# Brushless_2015RevB1_MagEnc.net
KiCad netlist of a schematic drawn in EAGLE
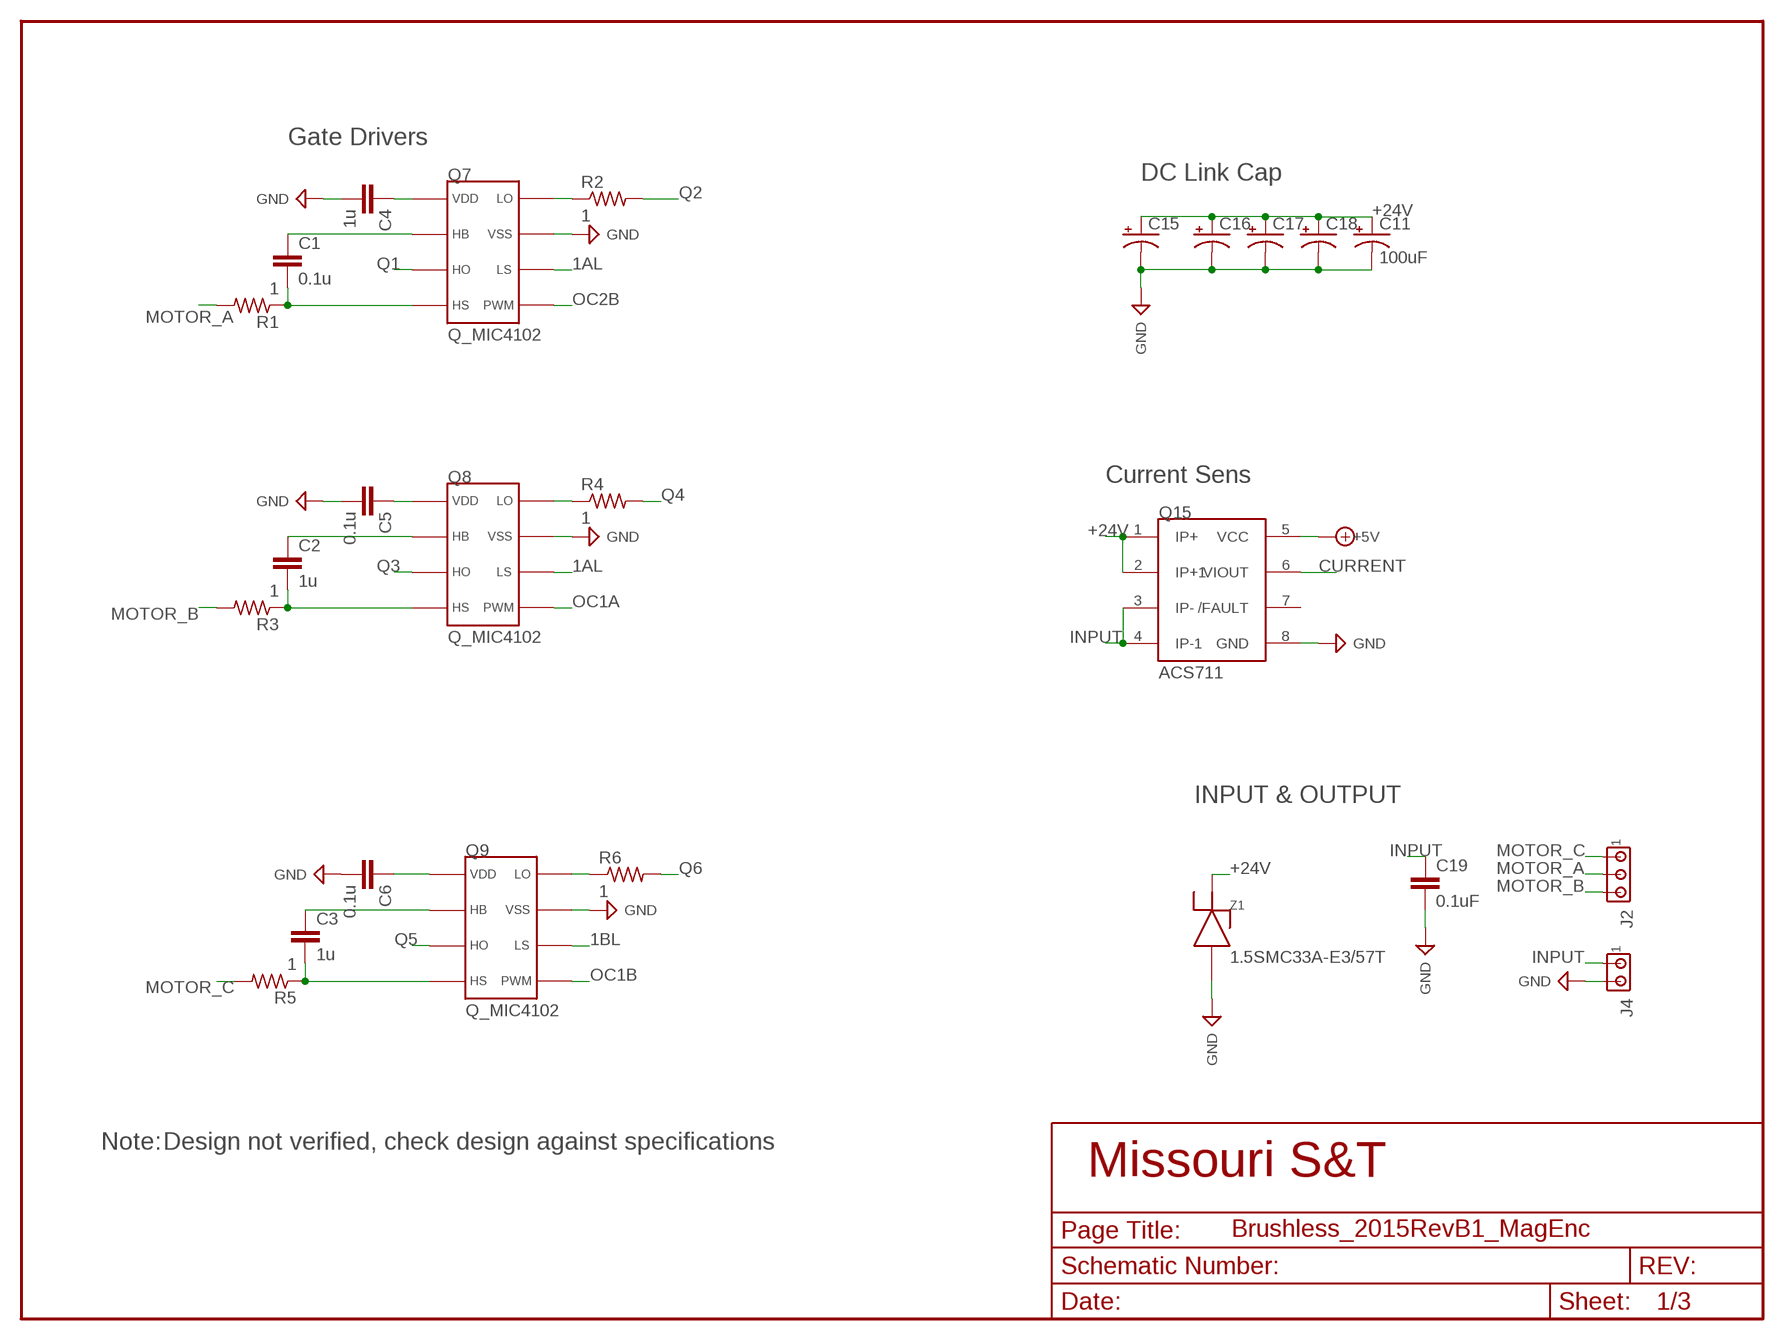
[diagram p0: schematic, sheet 1]
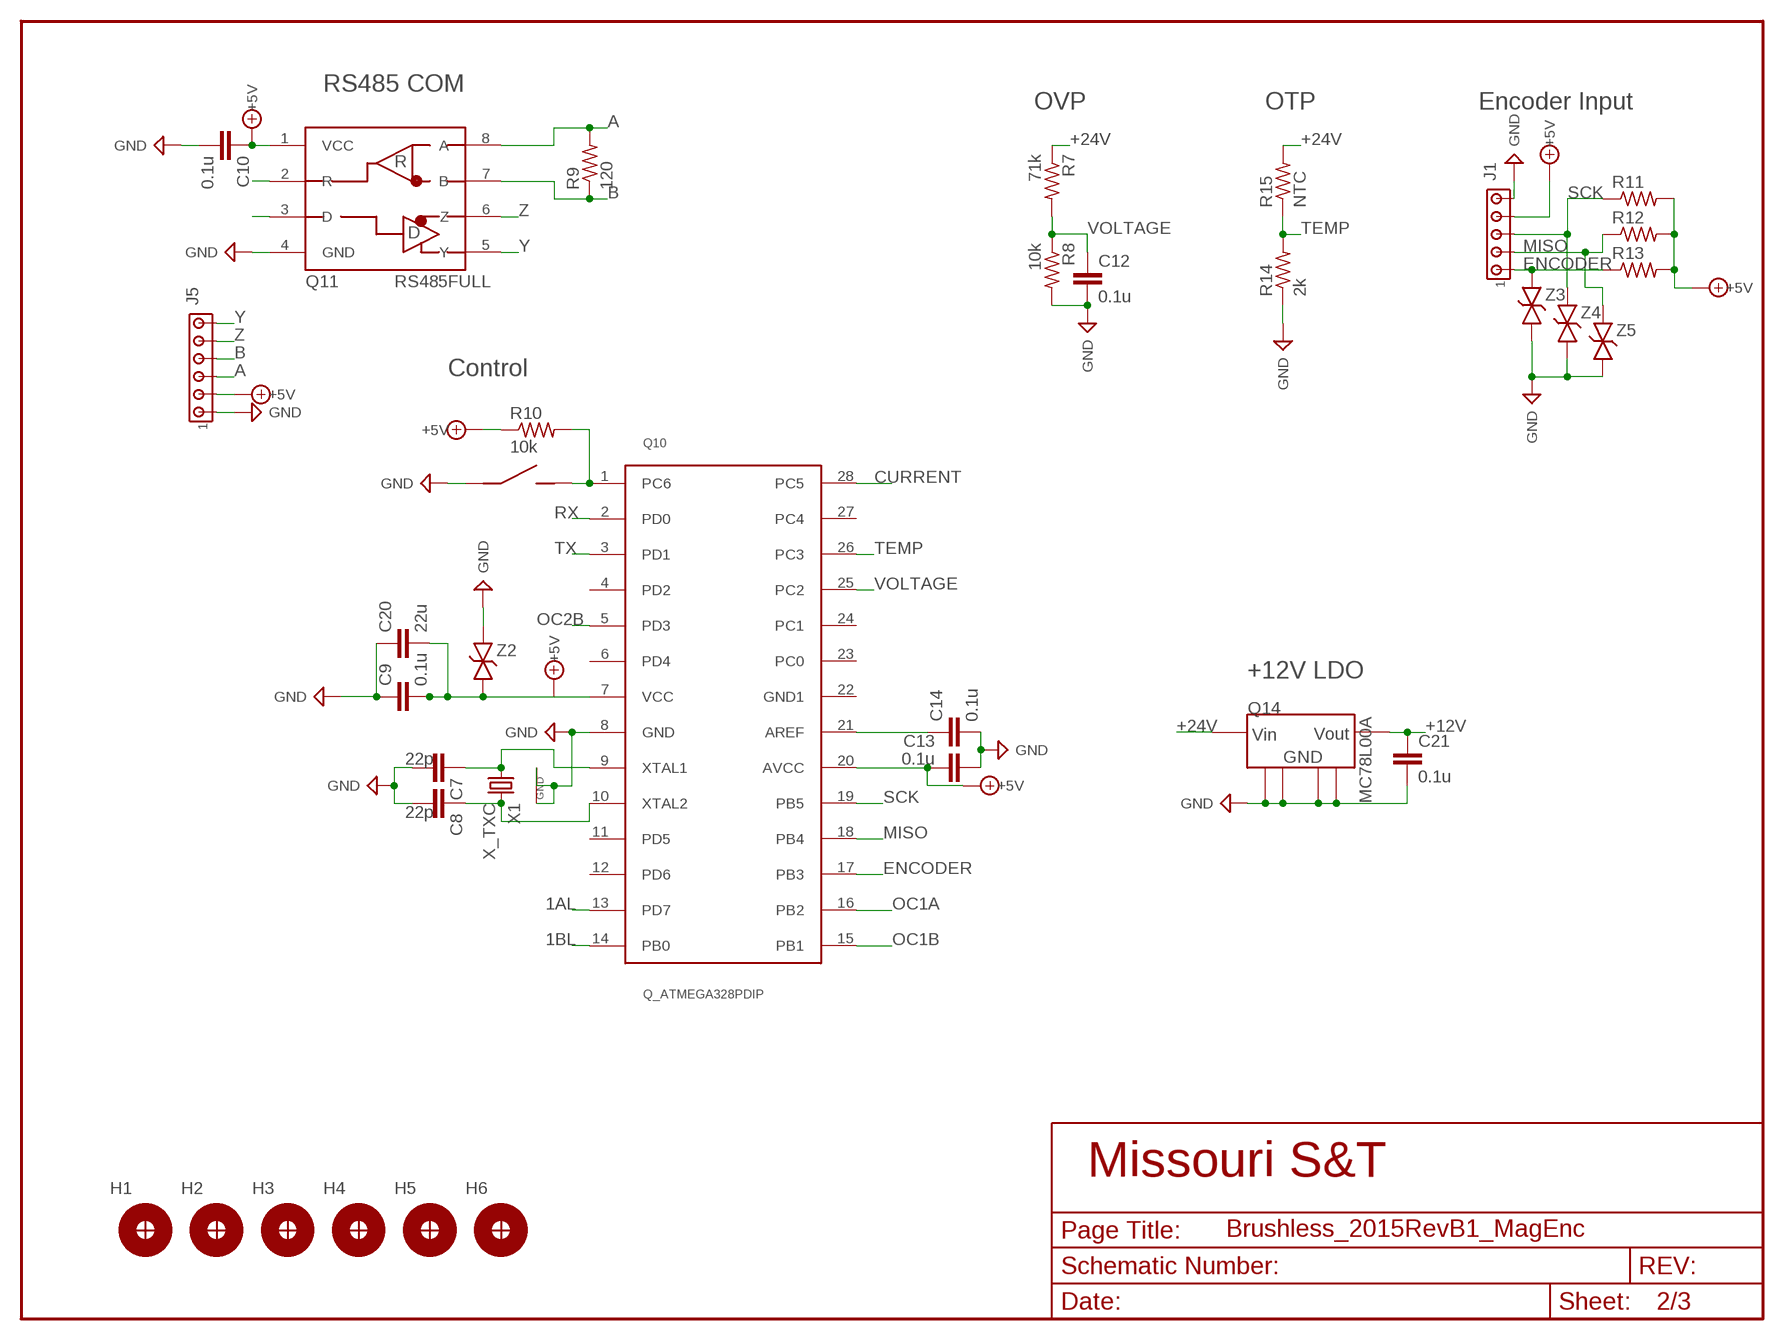
[diagram p1: schematic, sheet 2]
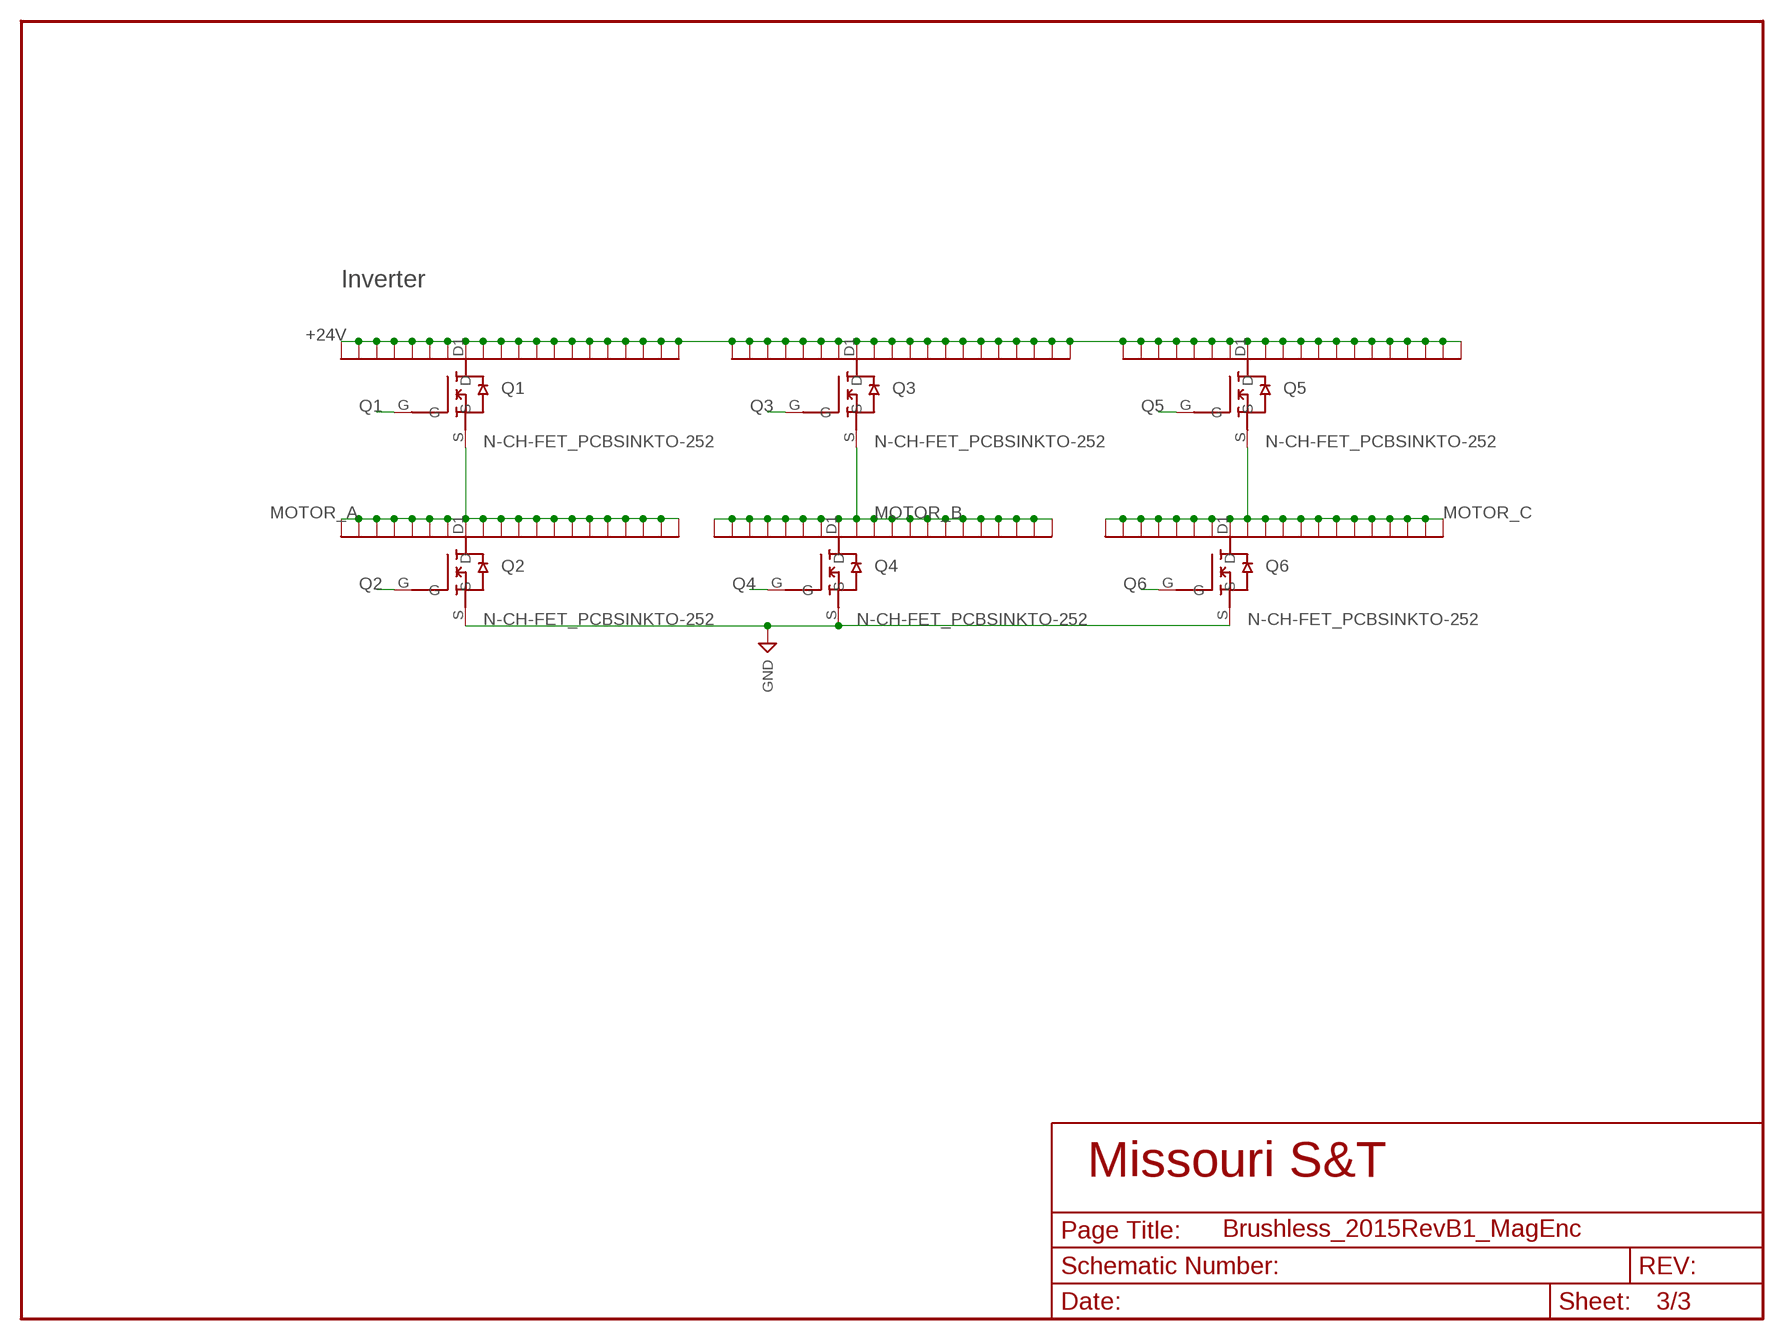
[diagram p2: schematic, sheet 3]

(export (version "E")
  (design (tool "Eeschema 10.0.6"))
  (components
    (comp (ref "C1")
      (value "0.1u")
      (footprint "eagle-import:C_1206")
      (libsource (lib "eagle-import") (part "Master_C_CAP_1206"))
    )
    (comp (ref "C2")
      (value "1u")
      (footprint "eagle-import:C_1206")
      (libsource (lib "eagle-import") (part "Master_C_CAP_1206"))
    )
    (comp (ref "C3")
      (value "1u")
      (footprint "eagle-import:C_1206")
      (libsource (lib "eagle-import") (part "Master_C_CAP_1206"))
    )
    (comp (ref "C4")
      (value "1u")
      (footprint "eagle-import:C_1206")
      (libsource (lib "eagle-import") (part "Master_C_CAP_1206"))
    )
    (comp (ref "C5")
      (value "0.1u")
      (footprint "eagle-import:C_1206")
      (libsource (lib "eagle-import") (part "Master_C_CAP_1206"))
    )
    (comp (ref "C6")
      (value "0.1u")
      (footprint "eagle-import:C_1206")
      (libsource (lib "eagle-import") (part "Master_C_CAP_1206"))
    )
    (comp (ref "C11")
      (value "100uF")
      (footprint "eagle-import:C_8MM")
      (libsource (lib "eagle-import") (part "CAP_POL8MM"))
    )
    (comp (ref "C15")
      (value "CAP_POL8MM")
      (footprint "eagle-import:C_8MM")
      (libsource (lib "eagle-import") (part "CAP_POL8MM"))
    )
    (comp (ref "C16")
      (value "CAP_POL8MM")
      (footprint "eagle-import:C_8MM")
      (libsource (lib "eagle-import") (part "CAP_POL8MM"))
    )
    (comp (ref "C17")
      (value "CAP_POL8MM")
      (footprint "eagle-import:C_8MM")
      (libsource (lib "eagle-import") (part "CAP_POL8MM"))
    )
    (comp (ref "C18")
      (value "CAP_POL8MM")
      (footprint "eagle-import:C_8MM")
      (libsource (lib "eagle-import") (part "CAP_POL8MM"))
    )
    (comp (ref "C19")
      (value "0.1uF")
      (footprint "eagle-import:C_1206")
      (libsource (lib "eagle-import") (part "C_CAP_1206"))
    )
    (comp (ref "J2")
      (value "J_MTA3P_156")
      (footprint "eagle-import:J_MTA156_3P")
      (libsource (lib "eagle-import") (part "J_MTA3P_156"))
    )
    (comp (ref "J4")
      (value "J_HDR1X2_MTA_156MIL")
      (footprint "eagle-import:J_MTA1X2_156MIL")
      (libsource (lib "eagle-import") (part "J_HDR1X2_MTA_156MIL"))
    )
    (comp (ref "Q7")
      (value "Q_MIC4102")
      (footprint "eagle-import:SOIC8")
      (libsource (lib "eagle-import") (part "Q_MIC4102"))
    )
    (comp (ref "Q8")
      (value "Q_MIC4102")
      (footprint "eagle-import:SOIC8")
      (libsource (lib "eagle-import") (part "Q_MIC4102"))
    )
    (comp (ref "Q9")
      (value "Q_MIC4102")
      (footprint "eagle-import:SOIC8")
      (libsource (lib "eagle-import") (part "Q_MIC4102"))
    )
    (comp (ref "Q15")
      (value "ACS711")
      (footprint "eagle-import:SOIC8")
      (libsource (lib "eagle-import") (part "ACS711SOIC"))
    )
    (comp (ref "R1")
      (value "1")
      (footprint "eagle-import:R_0805")
      (libsource (lib "eagle-import") (part "Master_R_RES_0805"))
    )
    (comp (ref "R2")
      (value "1")
      (footprint "eagle-import:R_0805")
      (libsource (lib "eagle-import") (part "Master_R_RES_0805"))
    )
    (comp (ref "R3")
      (value "1")
      (footprint "eagle-import:R_0805")
      (libsource (lib "eagle-import") (part "Master_R_RES_0805"))
    )
    (comp (ref "R4")
      (value "1")
      (footprint "eagle-import:R_0805")
      (libsource (lib "eagle-import") (part "Master_R_RES_0805"))
    )
    (comp (ref "R5")
      (value "1")
      (footprint "eagle-import:R_0805")
      (libsource (lib "eagle-import") (part "Master_R_RES_0805"))
    )
    (comp (ref "R6")
      (value "1")
      (footprint "eagle-import:R_0805")
      (libsource (lib "eagle-import") (part "Master_R_RES_0805"))
    )
    (comp (ref "Z1")
      (value "Z_TVSDO214")
      (footprint "eagle-import:DO-214AC")
      (libsource (lib "eagle-import") (part "Z_TVSDO214"))
    )
    (comp (ref "Q1")
      (value "N-CH-FET_PCBSINKTO-252")
      (footprint "eagle-import:TO-252-SINK")
      (libsource (lib "eagle-import") (part "N-CH-FET_PCBSINKTO-252"))
    )
    (comp (ref "Q2")
      (value "N-CH-FET_PCBSINKTO-252")
      (footprint "eagle-import:TO-252-SINK")
      (libsource (lib "eagle-import") (part "N-CH-FET_PCBSINKTO-252"))
    )
    (comp (ref "Q3")
      (value "N-CH-FET_PCBSINKTO-252")
      (footprint "eagle-import:TO-252-SINK")
      (libsource (lib "eagle-import") (part "N-CH-FET_PCBSINKTO-252"))
    )
    (comp (ref "Q4")
      (value "N-CH-FET_PCBSINKTO-252")
      (footprint "eagle-import:TO-252-SINK")
      (libsource (lib "eagle-import") (part "N-CH-FET_PCBSINKTO-252"))
    )
    (comp (ref "Q5")
      (value "N-CH-FET_PCBSINKTO-252")
      (footprint "eagle-import:TO-252-SINK")
      (libsource (lib "eagle-import") (part "N-CH-FET_PCBSINKTO-252"))
    )
    (comp (ref "Q6")
      (value "N-CH-FET_PCBSINKTO-252")
      (footprint "eagle-import:TO-252-SINK")
      (libsource (lib "eagle-import") (part "N-CH-FET_PCBSINKTO-252"))
    )
    (comp (ref "C7")
      (value "22p")
      (footprint "eagle-import:C_1206")
      (libsource (lib "eagle-import") (part "Master_C_CAP_1206"))
    )
    (comp (ref "C8")
      (value "22p")
      (footprint "eagle-import:C_1206")
      (libsource (lib "eagle-import") (part "Master_C_CAP_1206"))
    )
    (comp (ref "C9")
      (value "0.1u")
      (footprint "eagle-import:C_0805")
      (libsource (lib "eagle-import") (part "Master_C_CAP_0805"))
    )
    (comp (ref "C10")
      (value "0.1u")
      (footprint "eagle-import:C_0805")
      (libsource (lib "eagle-import") (part "Master_C_CAP_0805"))
    )
    (comp (ref "C12")
      (value "0.1u")
      (footprint "eagle-import:C_0805")
      (libsource (lib "eagle-import") (part "Master_C_CAP_0805"))
    )
    (comp (ref "C13")
      (value "0.1u")
      (footprint "eagle-import:C_1206")
      (libsource (lib "eagle-import") (part "C_CAP_1206"))
    )
    (comp (ref "C14")
      (value "0.1u")
      (footprint "eagle-import:C_0805")
      (libsource (lib "eagle-import") (part "Master_C_CAP_0805"))
    )
    (comp (ref "C20")
      (value "22u")
      (footprint "eagle-import:C_1206")
      (libsource (lib "eagle-import") (part "C_CAP_1206"))
    )
    (comp (ref "C21")
      (value "0.1u")
      (footprint "eagle-import:C_0805")
      (libsource (lib "eagle-import") (part "Master_C_CAP_0805"))
    )
    (comp (ref "H1")
      (value "H_MNTHOLE_#4")
      (footprint "eagle-import:H_MNTHOLE_#4")
      (libsource (lib "eagle-import") (part "H_MNTHOLE_#4"))
    )
    (comp (ref "H2")
      (value "H_MNTHOLE_#4")
      (footprint "eagle-import:H_MNTHOLE_#4")
      (libsource (lib "eagle-import") (part "H_MNTHOLE_#4"))
    )
    (comp (ref "H3")
      (value "H_MNTHOLE_#4")
      (footprint "eagle-import:H_MNTHOLE_#4")
      (libsource (lib "eagle-import") (part "H_MNTHOLE_#4"))
    )
    (comp (ref "H4")
      (value "H_MNTHOLE_#4")
      (footprint "eagle-import:H_MNTHOLE_#4")
      (libsource (lib "eagle-import") (part "H_MNTHOLE_#4"))
    )
    (comp (ref "H5")
      (value "H_MNTHOLE_#4")
      (footprint "eagle-import:H_MNTHOLE_#4")
      (libsource (lib "eagle-import") (part "H_MNTHOLE_#4"))
    )
    (comp (ref "H6")
      (value "H_MNTHOLE_#4")
      (footprint "eagle-import:H_MNTHOLE_#4")
      (libsource (lib "eagle-import") (part "H_MNTHOLE_#4"))
    )
    (comp (ref "J1")
      (value "J_MTA5P_100")
      (footprint "eagle-import:J_MTA100_5P")
      (libsource (lib "eagle-import") (part "J_MTA5P_100"))
    )
    (comp (ref "J3")
      (value "J_MC32857")
      (footprint "eagle-import:J_TOGGLE")
      (libsource (lib "eagle-import") (part "J_MC32857"))
    )
    (comp (ref "J5")
      (value "J_HDR1X6_MTA_100MIL")
      (footprint "eagle-import:J_MTA1X6_100MIL")
      (libsource (lib "eagle-import") (part "J_HDR1X6_MTA_100MIL"))
    )
    (comp (ref "Q10")
      (value "Q_ATMEGA328PDIP")
      (footprint "eagle-import:DIP28")
      (libsource (lib "eagle-import") (part "Q_ATMEGA328PDIP"))
    )
    (comp (ref "Q11")
      (value "RS485FULL")
      (footprint "eagle-import:SOIC8")
      (libsource (lib "eagle-import") (part "RS485FULL"))
    )
    (comp (ref "Q14")
      (value "MC78L00A")
      (footprint "eagle-import:SOIC8")
      (libsource (lib "eagle-import") (part "Q_LDOSOIC"))
    )
    (comp (ref "R7")
      (value "71k")
      (footprint "eagle-import:R_0805")
      (libsource (lib "eagle-import") (part "Master_R_RES_0805"))
    )
    (comp (ref "R8")
      (value "10k")
      (footprint "eagle-import:R_0805")
      (libsource (lib "eagle-import") (part "Master_R_RES_0805"))
    )
    (comp (ref "R9")
      (value "120")
      (footprint "eagle-import:R_0805")
      (libsource (lib "eagle-import") (part "Master_R_RES_0805"))
    )
    (comp (ref "R10")
      (value "10k")
      (footprint "eagle-import:R_0805")
      (libsource (lib "eagle-import") (part "R_RES_0805"))
    )
    (comp (ref "R11")
      (value "R_RES_1206")
      (footprint "eagle-import:R_1206")
      (libsource (lib "eagle-import") (part "R_RES_1206"))
    )
    (comp (ref "R12")
      (value "R_RES_1206")
      (footprint "eagle-import:R_1206")
      (libsource (lib "eagle-import") (part "R_RES_1206"))
    )
    (comp (ref "R13")
      (value "R_RES_1206")
      (footprint "eagle-import:R_1206")
      (libsource (lib "eagle-import") (part "R_RES_1206"))
    )
    (comp (ref "R14")
      (value "2k")
      (footprint "eagle-import:R_0805")
      (libsource (lib "eagle-import") (part "R_RES_0805"))
    )
    (comp (ref "R15")
      (value "NTC")
      (footprint "eagle-import:R_0805")
      (libsource (lib "eagle-import") (part "R_RES_0805"))
    )
    (comp (ref "X1")
      (value "X_TXC")
      (footprint "eagle-import:SMD_CRYSTAL")
      (libsource (lib "eagle-import") (part "X_TXC"))
    )
    (comp (ref "Z2")
      (value "Z_ESD0603")
      (footprint "eagle-import:0603")
      (libsource (lib "eagle-import") (part "Z_ESD0603"))
    )
    (comp (ref "Z3")
      (value "Z_ESD0603")
      (footprint "eagle-import:0603")
      (libsource (lib "eagle-import") (part "Z_ESD0603"))
    )
    (comp (ref "Z4")
      (value "Z_ESD0603")
      (footprint "eagle-import:0603")
      (libsource (lib "eagle-import") (part "Z_ESD0603"))
    )
    (comp (ref "Z5")
      (value "Z_ESD0603")
      (footprint "eagle-import:0603")
      (libsource (lib "eagle-import") (part "Z_ESD0603"))
    )
  )
  (nets
    (net (code "1") (name "+5V") (class "Default")
      (node (ref "C10") (pin "1") (pinfunction "1_1") (pintype "passive"))
      (node (ref "C13") (pin "1") (pinfunction "1_1") (pintype "passive"))
      (node (ref "C20") (pin "2") (pinfunction "2_2") (pintype "passive"))
      (node (ref "C9") (pin "2") (pinfunction "2_2") (pintype "passive"))
      (node (ref "J1") (pin "4") (pinfunction "4_4") (pintype "passive"))
      (node (ref "J5") (pin "2") (pinfunction "2_2") (pintype "passive"))
      (node (ref "Q10") (pin "20") (pinfunction "AVCC_20") (pintype "bidirectional"))
      (node (ref "Q10") (pin "7") (pinfunction "VCC_7") (pintype "bidirectional"))
      (node (ref "Q11") (pin "1") (pinfunction "VCC_1") (pintype "bidirectional"))
      (node (ref "Q15") (pin "5") (pinfunction "VCC_5") (pintype "bidirectional"))
      (node (ref "R10") (pin "1") (pinfunction "1_1") (pintype "passive"))
      (node (ref "R11") (pin "2") (pinfunction "2_2") (pintype "passive"))
      (node (ref "R12") (pin "2") (pinfunction "2_2") (pintype "passive"))
      (node (ref "R13") (pin "2") (pinfunction "2_2") (pintype "passive"))
      (node (ref "Z2") (pin "1") (pinfunction "P$1_1") (pintype "bidirectional"))
    )
    (net (code "2") (name "+12V") (class "Default")
      (node (ref "C21") (pin "1") (pinfunction "1_1") (pintype "passive"))
      (node (ref "C4") (pin "1") (pinfunction "1_1") (pintype "passive"))
      (node (ref "C5") (pin "1") (pinfunction "1_1") (pintype "passive"))
      (node (ref "C6") (pin "1") (pinfunction "1_1") (pintype "passive"))
      (node (ref "Q14") (pin "1") (pinfunction "VOUT_1") (pintype "bidirectional"))
      (node (ref "Q7") (pin "1") (pinfunction "VDD_1") (pintype "bidirectional"))
      (node (ref "Q8") (pin "1") (pinfunction "VDD_1") (pintype "bidirectional"))
      (node (ref "Q9") (pin "1") (pinfunction "VDD_1") (pintype "bidirectional"))
    )
    (net (code "3") (name "+24V") (class "Default")
      (node (ref "C11") (pin "+") (pinfunction "+_+") (pintype "passive"))
      (node (ref "C15") (pin "+") (pinfunction "+_+") (pintype "passive"))
      (node (ref "C16") (pin "+") (pinfunction "+_+") (pintype "passive"))
      (node (ref "C17") (pin "+") (pinfunction "+_+") (pintype "passive"))
      (node (ref "C18") (pin "+") (pinfunction "+_+") (pintype "passive"))
      (node (ref "Q1") (pin "D1") (pinfunction "D_D1") (pintype "bidirectional"))
      (node (ref "Q1") (pin "D10") (pinfunction "P$9_D10") (pintype "bidirectional"))
      (node (ref "Q1") (pin "D11") (pinfunction "P$10_D11") (pintype "bidirectional"))
      (node (ref "Q1") (pin "D12") (pinfunction "P$11_D12") (pintype "bidirectional"))
      (node (ref "Q1") (pin "D13") (pinfunction "P$12_D13") (pintype "bidirectional"))
      (node (ref "Q1") (pin "D14") (pinfunction "P$13_D14") (pintype "bidirectional"))
      (node (ref "Q1") (pin "D15") (pinfunction "P$14_D15") (pintype "bidirectional"))
      (node (ref "Q1") (pin "D16") (pinfunction "P$15_D16") (pintype "bidirectional"))
      (node (ref "Q1") (pin "D17") (pinfunction "P$16_D17") (pintype "bidirectional"))
      (node (ref "Q1") (pin "D18") (pinfunction "P$17_D18") (pintype "bidirectional"))
      (node (ref "Q1") (pin "D19") (pinfunction "P$18_D19") (pintype "bidirectional"))
      (node (ref "Q1") (pin "D2") (pinfunction "P$1_D2") (pintype "bidirectional"))
      (node (ref "Q1") (pin "D20") (pinfunction "P$19_D20") (pintype "bidirectional"))
      (node (ref "Q1") (pin "D3") (pinfunction "P$2_D3") (pintype "bidirectional"))
      (node (ref "Q1") (pin "D4") (pinfunction "P$3_D4") (pintype "bidirectional"))
      (node (ref "Q1") (pin "D5") (pinfunction "P$4_D5") (pintype "bidirectional"))
      (node (ref "Q1") (pin "D6") (pinfunction "P$5_D6") (pintype "bidirectional"))
      (node (ref "Q1") (pin "D7") (pinfunction "P$6_D7") (pintype "bidirectional"))
      (node (ref "Q1") (pin "D8") (pinfunction "P$7_D8") (pintype "bidirectional"))
      (node (ref "Q1") (pin "D9") (pinfunction "P$8_D9") (pintype "bidirectional"))
      (node (ref "Q14") (pin "8") (pinfunction "VIN_8") (pintype "bidirectional"))
      (node (ref "Q15") (pin "1") (pinfunction "IP+_1") (pintype "bidirectional"))
      (node (ref "Q15") (pin "2") (pinfunction "IP+1_2") (pintype "bidirectional"))
      (node (ref "Q3") (pin "D1") (pinfunction "D_D1") (pintype "bidirectional"))
      (node (ref "Q3") (pin "D10") (pinfunction "P$9_D10") (pintype "bidirectional"))
      (node (ref "Q3") (pin "D11") (pinfunction "P$10_D11") (pintype "bidirectional"))
      (node (ref "Q3") (pin "D12") (pinfunction "P$11_D12") (pintype "bidirectional"))
      (node (ref "Q3") (pin "D13") (pinfunction "P$12_D13") (pintype "bidirectional"))
      (node (ref "Q3") (pin "D14") (pinfunction "P$13_D14") (pintype "bidirectional"))
      (node (ref "Q3") (pin "D15") (pinfunction "P$14_D15") (pintype "bidirectional"))
      (node (ref "Q3") (pin "D16") (pinfunction "P$15_D16") (pintype "bidirectional"))
      (node (ref "Q3") (pin "D17") (pinfunction "P$16_D17") (pintype "bidirectional"))
      (node (ref "Q3") (pin "D18") (pinfunction "P$17_D18") (pintype "bidirectional"))
      (node (ref "Q3") (pin "D19") (pinfunction "P$18_D19") (pintype "bidirectional"))
      (node (ref "Q3") (pin "D2") (pinfunction "P$1_D2") (pintype "bidirectional"))
      (node (ref "Q3") (pin "D20") (pinfunction "P$19_D20") (pintype "bidirectional"))
      (node (ref "Q3") (pin "D3") (pinfunction "P$2_D3") (pintype "bidirectional"))
      (node (ref "Q3") (pin "D4") (pinfunction "P$3_D4") (pintype "bidirectional"))
      (node (ref "Q3") (pin "D5") (pinfunction "P$4_D5") (pintype "bidirectional"))
      (node (ref "Q3") (pin "D6") (pinfunction "P$5_D6") (pintype "bidirectional"))
      (node (ref "Q3") (pin "D7") (pinfunction "P$6_D7") (pintype "bidirectional"))
      (node (ref "Q3") (pin "D8") (pinfunction "P$7_D8") (pintype "bidirectional"))
      (node (ref "Q3") (pin "D9") (pinfunction "P$8_D9") (pintype "bidirectional"))
      (node (ref "Q5") (pin "D1") (pinfunction "D_D1") (pintype "bidirectional"))
      (node (ref "Q5") (pin "D10") (pinfunction "P$9_D10") (pintype "bidirectional"))
      (node (ref "Q5") (pin "D11") (pinfunction "P$10_D11") (pintype "bidirectional"))
      (node (ref "Q5") (pin "D12") (pinfunction "P$11_D12") (pintype "bidirectional"))
      (node (ref "Q5") (pin "D13") (pinfunction "P$12_D13") (pintype "bidirectional"))
      (node (ref "Q5") (pin "D14") (pinfunction "P$13_D14") (pintype "bidirectional"))
      (node (ref "Q5") (pin "D15") (pinfunction "P$14_D15") (pintype "bidirectional"))
      (node (ref "Q5") (pin "D16") (pinfunction "P$15_D16") (pintype "bidirectional"))
      (node (ref "Q5") (pin "D17") (pinfunction "P$16_D17") (pintype "bidirectional"))
      (node (ref "Q5") (pin "D18") (pinfunction "P$17_D18") (pintype "bidirectional"))
      (node (ref "Q5") (pin "D19") (pinfunction "P$18_D19") (pintype "bidirectional"))
      (node (ref "Q5") (pin "D2") (pinfunction "P$1_D2") (pintype "bidirectional"))
      (node (ref "Q5") (pin "D20") (pinfunction "P$19_D20") (pintype "bidirectional"))
      (node (ref "Q5") (pin "D3") (pinfunction "P$2_D3") (pintype "bidirectional"))
      (node (ref "Q5") (pin "D4") (pinfunction "P$3_D4") (pintype "bidirectional"))
      (node (ref "Q5") (pin "D5") (pinfunction "P$4_D5") (pintype "bidirectional"))
      (node (ref "Q5") (pin "D6") (pinfunction "P$5_D6") (pintype "bidirectional"))
      (node (ref "Q5") (pin "D7") (pinfunction "P$6_D7") (pintype "bidirectional"))
      (node (ref "Q5") (pin "D8") (pinfunction "P$7_D8") (pintype "bidirectional"))
      (node (ref "Q5") (pin "D9") (pinfunction "P$8_D9") (pintype "bidirectional"))
      (node (ref "R15") (pin "2") (pinfunction "2_2") (pintype "passive"))
      (node (ref "R7") (pin "1") (pinfunction "1_1") (pintype "passive"))
      (node (ref "Z1") (pin "C") (pinfunction "C_C") (pintype "bidirectional"))
    )
    (net (code "4") (name "1AL") (class "Default")
      (node (ref "Q10") (pin "13") (pinfunction "PD7_13") (pintype "bidirectional"))
      (node (ref "Q7") (pin "6") (pinfunction "LS_6") (pintype "bidirectional"))
      (node (ref "Q8") (pin "6") (pinfunction "LS_6") (pintype "bidirectional"))
    )
    (net (code "5") (name "1BL") (class "Default")
      (node (ref "Q10") (pin "14") (pinfunction "PB0_14") (pintype "bidirectional"))
      (node (ref "Q9") (pin "6") (pinfunction "LS_6") (pintype "bidirectional"))
    )
    (net (code "6") (name "A") (class "Default")
      (node (ref "J5") (pin "3") (pinfunction "3_3") (pintype "passive"))
      (node (ref "Q11") (pin "8") (pinfunction "A_8") (pintype "bidirectional"))
      (node (ref "R9") (pin "2") (pinfunction "2_2") (pintype "passive"))
    )
    (net (code "7") (name "B") (class "Default")
      (node (ref "J5") (pin "4") (pinfunction "4_4") (pintype "passive"))
      (node (ref "Q11") (pin "7") (pinfunction "B_7") (pintype "bidirectional"))
      (node (ref "R9") (pin "1") (pinfunction "1_1") (pintype "passive"))
    )
    (net (code "8") (name "CURRENT") (class "Default")
      (node (ref "Q10") (pin "28") (pinfunction "PC5_28") (pintype "bidirectional"))
      (node (ref "Q15") (pin "6") (pinfunction "VIOUT_6") (pintype "bidirectional"))
    )
    (net (code "9") (name "ENCODER") (class "Default")
      (node (ref "J1") (pin "1") (pinfunction "1_1") (pintype "passive"))
      (node (ref "Q10") (pin "17") (pinfunction "PB3_17") (pintype "bidirectional"))
      (node (ref "R13") (pin "1") (pinfunction "1_1") (pintype "passive"))
      (node (ref "Z3") (pin "2") (pinfunction "P$2_2") (pintype "bidirectional"))
    )
    (net (code "10") (name "GND") (class "Default")
      (node (ref "C10") (pin "2") (pinfunction "2_2") (pintype "passive"))
      (node (ref "C11") (pin "-") (pinfunction "-_-") (pintype "passive"))
      (node (ref "C12") (pin "2") (pinfunction "2_2") (pintype "passive"))
      (node (ref "C13") (pin "2") (pinfunction "2_2") (pintype "passive"))
      (node (ref "C14") (pin "2") (pinfunction "2_2") (pintype "passive"))
      (node (ref "C15") (pin "-") (pinfunction "-_-") (pintype "passive"))
      (node (ref "C16") (pin "-") (pinfunction "-_-") (pintype "passive"))
      (node (ref "C17") (pin "-") (pinfunction "-_-") (pintype "passive"))
      (node (ref "C18") (pin "-") (pinfunction "-_-") (pintype "passive"))
      (node (ref "C19") (pin "2") (pinfunction "2_2") (pintype "passive"))
      (node (ref "C20") (pin "1") (pinfunction "1_1") (pintype "passive"))
      (node (ref "C21") (pin "2") (pinfunction "2_2") (pintype "passive"))
      (node (ref "C4") (pin "2") (pinfunction "2_2") (pintype "passive"))
      (node (ref "C5") (pin "2") (pinfunction "2_2") (pintype "passive"))
      (node (ref "C6") (pin "2") (pinfunction "2_2") (pintype "passive"))
      (node (ref "C7") (pin "2") (pinfunction "2_2") (pintype "passive"))
      (node (ref "C8") (pin "2") (pinfunction "2_2") (pintype "passive"))
      (node (ref "C9") (pin "1") (pinfunction "1_1") (pintype "passive"))
      (node (ref "J1") (pin "5") (pinfunction "5_5") (pintype "passive"))
      (node (ref "J3") (pin "P$1") (pinfunction "1_P$1") (pintype "bidirectional"))
      (node (ref "J4") (pin "2") (pinfunction "2_2") (pintype "passive"))
      (node (ref "J5") (pin "1") (pinfunction "1_1") (pintype "passive"))
      (node (ref "Q10") (pin "8") (pinfunction "GND_8") (pintype "bidirectional"))
      (node (ref "Q11") (pin "4") (pinfunction "GND_4") (pintype "bidirectional"))
      (node (ref "Q14") (pin "2") (pinfunction "GND_2") (pintype "bidirectional"))
      (node (ref "Q14") (pin "3") (pinfunction "GND1_3") (pintype "bidirectional"))
      (node (ref "Q14") (pin "6") (pinfunction "GND3_6") (pintype "bidirectional"))
      (node (ref "Q14") (pin "7") (pinfunction "GND2_7") (pintype "bidirectional"))
      (node (ref "Q15") (pin "8") (pinfunction "GND_8") (pintype "bidirectional"))
      (node (ref "Q2") (pin "S") (pinfunction "S_S") (pintype "bidirectional"))
      (node (ref "Q4") (pin "S") (pinfunction "S_S") (pintype "bidirectional"))
      (node (ref "Q6") (pin "S") (pinfunction "S_S") (pintype "bidirectional"))
      (node (ref "Q7") (pin "7") (pinfunction "VSS_7") (pintype "bidirectional"))
      (node (ref "Q8") (pin "7") (pinfunction "VSS_7") (pintype "bidirectional"))
      (node (ref "Q9") (pin "7") (pinfunction "VSS_7") (pintype "bidirectional"))
      (node (ref "R14") (pin "1") (pinfunction "1_1") (pintype "passive"))
      (node (ref "R8") (pin "2") (pinfunction "2_2") (pintype "passive"))
      (node (ref "X1") (pin "2") (pinfunction "GND1_2") (pintype "bidirectional"))
      (node (ref "X1") (pin "4") (pinfunction "GND2_4") (pintype "bidirectional"))
      (node (ref "Z1") (pin "A") (pinfunction "A_A") (pintype "bidirectional"))
      (node (ref "Z2") (pin "2") (pinfunction "P$2_2") (pintype "bidirectional"))
      (node (ref "Z3") (pin "1") (pinfunction "P$1_1") (pintype "bidirectional"))
      (node (ref "Z4") (pin "1") (pinfunction "P$1_1") (pintype "bidirectional"))
      (node (ref "Z5") (pin "1") (pinfunction "P$1_1") (pintype "bidirectional"))
    )
    (net (code "11") (name "INPUT") (class "Default")
      (node (ref "C19") (pin "1") (pinfunction "1_1") (pintype "passive"))
      (node (ref "J4") (pin "1") (pinfunction "1_1") (pintype "passive"))
      (node (ref "Q15") (pin "3") (pinfunction "IP-_3") (pintype "bidirectional"))
      (node (ref "Q15") (pin "4") (pinfunction "IP-1_4") (pintype "bidirectional"))
    )
    (net (code "12") (name "MISO") (class "Default")
      (node (ref "J1") (pin "2") (pinfunction "2_2") (pintype "passive"))
      (node (ref "Q10") (pin "18") (pinfunction "PB4_18") (pintype "bidirectional"))
      (node (ref "R12") (pin "1") (pinfunction "1_1") (pintype "passive"))
      (node (ref "Z5") (pin "2") (pinfunction "P$2_2") (pintype "bidirectional"))
    )
    (net (code "13") (name "MOTOR_A") (class "Default")
      (node (ref "J2") (pin "2") (pinfunction "2_2") (pintype "passive"))
      (node (ref "Q1") (pin "S") (pinfunction "S_S") (pintype "bidirectional"))
      (node (ref "Q2") (pin "D1") (pinfunction "D_D1") (pintype "bidirectional"))
      (node (ref "Q2") (pin "D10") (pinfunction "P$9_D10") (pintype "bidirectional"))
      (node (ref "Q2") (pin "D11") (pinfunction "P$10_D11") (pintype "bidirectional"))
      (node (ref "Q2") (pin "D12") (pinfunction "P$11_D12") (pintype "bidirectional"))
      (node (ref "Q2") (pin "D13") (pinfunction "P$12_D13") (pintype "bidirectional"))
      (node (ref "Q2") (pin "D14") (pinfunction "P$13_D14") (pintype "bidirectional"))
      (node (ref "Q2") (pin "D15") (pinfunction "P$14_D15") (pintype "bidirectional"))
      (node (ref "Q2") (pin "D16") (pinfunction "P$15_D16") (pintype "bidirectional"))
      (node (ref "Q2") (pin "D17") (pinfunction "P$16_D17") (pintype "bidirectional"))
      (node (ref "Q2") (pin "D18") (pinfunction "P$17_D18") (pintype "bidirectional"))
      (node (ref "Q2") (pin "D19") (pinfunction "P$18_D19") (pintype "bidirectional"))
      (node (ref "Q2") (pin "D2") (pinfunction "P$1_D2") (pintype "bidirectional"))
      (node (ref "Q2") (pin "D20") (pinfunction "P$19_D20") (pintype "bidirectional"))
      (node (ref "Q2") (pin "D3") (pinfunction "P$2_D3") (pintype "bidirectional"))
      (node (ref "Q2") (pin "D4") (pinfunction "P$3_D4") (pintype "bidirectional"))
      (node (ref "Q2") (pin "D5") (pinfunction "P$4_D5") (pintype "bidirectional"))
      (node (ref "Q2") (pin "D6") (pinfunction "P$5_D6") (pintype "bidirectional"))
      (node (ref "Q2") (pin "D7") (pinfunction "P$6_D7") (pintype "bidirectional"))
      (node (ref "Q2") (pin "D8") (pinfunction "P$7_D8") (pintype "bidirectional"))
      (node (ref "Q2") (pin "D9") (pinfunction "P$8_D9") (pintype "bidirectional"))
      (node (ref "R1") (pin "2") (pinfunction "2_2") (pintype "passive"))
    )
    (net (code "14") (name "MOTOR_B") (class "Default")
      (node (ref "J2") (pin "3") (pinfunction "3_3") (pintype "passive"))
      (node (ref "Q3") (pin "S") (pinfunction "S_S") (pintype "bidirectional"))
      (node (ref "Q4") (pin "D1") (pinfunction "D_D1") (pintype "bidirectional"))
      (node (ref "Q4") (pin "D10") (pinfunction "P$9_D10") (pintype "bidirectional"))
      (node (ref "Q4") (pin "D11") (pinfunction "P$10_D11") (pintype "bidirectional"))
      (node (ref "Q4") (pin "D12") (pinfunction "P$11_D12") (pintype "bidirectional"))
      (node (ref "Q4") (pin "D13") (pinfunction "P$12_D13") (pintype "bidirectional"))
      (node (ref "Q4") (pin "D14") (pinfunction "P$13_D14") (pintype "bidirectional"))
      (node (ref "Q4") (pin "D15") (pinfunction "P$14_D15") (pintype "bidirectional"))
      (node (ref "Q4") (pin "D16") (pinfunction "P$15_D16") (pintype "bidirectional"))
      (node (ref "Q4") (pin "D17") (pinfunction "P$16_D17") (pintype "bidirectional"))
      (node (ref "Q4") (pin "D18") (pinfunction "P$17_D18") (pintype "bidirectional"))
      (node (ref "Q4") (pin "D19") (pinfunction "P$18_D19") (pintype "bidirectional"))
      (node (ref "Q4") (pin "D2") (pinfunction "P$1_D2") (pintype "bidirectional"))
      (node (ref "Q4") (pin "D20") (pinfunction "P$19_D20") (pintype "bidirectional"))
      (node (ref "Q4") (pin "D3") (pinfunction "P$2_D3") (pintype "bidirectional"))
      (node (ref "Q4") (pin "D4") (pinfunction "P$3_D4") (pintype "bidirectional"))
      (node (ref "Q4") (pin "D5") (pinfunction "P$4_D5") (pintype "bidirectional"))
      (node (ref "Q4") (pin "D6") (pinfunction "P$5_D6") (pintype "bidirectional"))
      (node (ref "Q4") (pin "D7") (pinfunction "P$6_D7") (pintype "bidirectional"))
      (node (ref "Q4") (pin "D8") (pinfunction "P$7_D8") (pintype "bidirectional"))
      (node (ref "Q4") (pin "D9") (pinfunction "P$8_D9") (pintype "bidirectional"))
      (node (ref "R3") (pin "2") (pinfunction "2_2") (pintype "passive"))
    )
    (net (code "15") (name "MOTOR_C") (class "Default")
      (node (ref "J2") (pin "1") (pinfunction "1_1") (pintype "passive"))
      (node (ref "Q5") (pin "S") (pinfunction "S_S") (pintype "bidirectional"))
      (node (ref "Q6") (pin "D1") (pinfunction "D_D1") (pintype "bidirectional"))
      (node (ref "Q6") (pin "D10") (pinfunction "P$9_D10") (pintype "bidirectional"))
      (node (ref "Q6") (pin "D11") (pinfunction "P$10_D11") (pintype "bidirectional"))
      (node (ref "Q6") (pin "D12") (pinfunction "P$11_D12") (pintype "bidirectional"))
      (node (ref "Q6") (pin "D13") (pinfunction "P$12_D13") (pintype "bidirectional"))
      (node (ref "Q6") (pin "D14") (pinfunction "P$13_D14") (pintype "bidirectional"))
      (node (ref "Q6") (pin "D15") (pinfunction "P$14_D15") (pintype "bidirectional"))
      (node (ref "Q6") (pin "D16") (pinfunction "P$15_D16") (pintype "bidirectional"))
      (node (ref "Q6") (pin "D17") (pinfunction "P$16_D17") (pintype "bidirectional"))
      (node (ref "Q6") (pin "D18") (pinfunction "P$17_D18") (pintype "bidirectional"))
      (node (ref "Q6") (pin "D19") (pinfunction "P$18_D19") (pintype "bidirectional"))
      (node (ref "Q6") (pin "D2") (pinfunction "P$1_D2") (pintype "bidirectional"))
      (node (ref "Q6") (pin "D20") (pinfunction "P$19_D20") (pintype "bidirectional"))
      (node (ref "Q6") (pin "D3") (pinfunction "P$2_D3") (pintype "bidirectional"))
      (node (ref "Q6") (pin "D4") (pinfunction "P$3_D4") (pintype "bidirectional"))
      (node (ref "Q6") (pin "D5") (pinfunction "P$4_D5") (pintype "bidirectional"))
      (node (ref "Q6") (pin "D6") (pinfunction "P$5_D6") (pintype "bidirectional"))
      (node (ref "Q6") (pin "D7") (pinfunction "P$6_D7") (pintype "bidirectional"))
      (node (ref "Q6") (pin "D8") (pinfunction "P$7_D8") (pintype "bidirectional"))
      (node (ref "Q6") (pin "D9") (pinfunction "P$8_D9") (pintype "bidirectional"))
      (node (ref "R5") (pin "2") (pinfunction "2_2") (pintype "passive"))
    )
    (net (code "16") (name "Net-(J3-2)") (class "Default")
      (node (ref "J3") (pin "P$2") (pinfunction "2_P$2") (pintype "bidirectional"))
      (node (ref "Q10") (pin "1") (pinfunction "PC6_1") (pintype "bidirectional"))
      (node (ref "R10") (pin "2") (pinfunction "2_2") (pintype "passive"))
    )
    (net (code "17") (name "Net-(Q7-HB)") (class "Default")
      (node (ref "C1") (pin "1") (pinfunction "1_1") (pintype "passive"))
      (node (ref "Q7") (pin "2") (pinfunction "HB_2") (pintype "bidirectional"))
    )
    (net (code "18") (name "Net-(Q7-HS)") (class "Default")
      (node (ref "C1") (pin "2") (pinfunction "2_2") (pintype "passive"))
      (node (ref "Q7") (pin "4") (pinfunction "HS_4") (pintype "bidirectional"))
      (node (ref "R1") (pin "1") (pinfunction "1_1") (pintype "passive"))
    )
    (net (code "19") (name "Net-(Q7-LO)") (class "Default")
      (node (ref "Q7") (pin "8") (pinfunction "LO_8") (pintype "bidirectional"))
      (node (ref "R2") (pin "1") (pinfunction "1_1") (pintype "passive"))
    )
    (net (code "20") (name "Net-(Q8-HB)") (class "Default")
      (node (ref "C2") (pin "1") (pinfunction "1_1") (pintype "passive"))
      (node (ref "Q8") (pin "2") (pinfunction "HB_2") (pintype "bidirectional"))
    )
    (net (code "21") (name "Net-(Q8-HS)") (class "Default")
      (node (ref "C2") (pin "2") (pinfunction "2_2") (pintype "passive"))
      (node (ref "Q8") (pin "4") (pinfunction "HS_4") (pintype "bidirectional"))
      (node (ref "R3") (pin "1") (pinfunction "1_1") (pintype "passive"))
    )
    (net (code "22") (name "Net-(Q8-LO)") (class "Default")
      (node (ref "Q8") (pin "8") (pinfunction "LO_8") (pintype "bidirectional"))
      (node (ref "R4") (pin "1") (pinfunction "1_1") (pintype "passive"))
    )
    (net (code "23") (name "Net-(Q9-HB)") (class "Default")
      (node (ref "C3") (pin "1") (pinfunction "1_1") (pintype "passive"))
      (node (ref "Q9") (pin "2") (pinfunction "HB_2") (pintype "bidirectional"))
    )
    (net (code "24") (name "Net-(Q9-HS)") (class "Default")
      (node (ref "C3") (pin "2") (pinfunction "2_2") (pintype "passive"))
      (node (ref "Q9") (pin "4") (pinfunction "HS_4") (pintype "bidirectional"))
      (node (ref "R5") (pin "1") (pinfunction "1_1") (pintype "passive"))
    )
    (net (code "25") (name "Net-(Q9-LO)") (class "Default")
      (node (ref "Q9") (pin "8") (pinfunction "LO_8") (pintype "bidirectional"))
      (node (ref "R6") (pin "1") (pinfunction "1_1") (pintype "passive"))
    )
    (net (code "26") (name "Net-(Q10-AREF)") (class "Default")
      (node (ref "C14") (pin "1") (pinfunction "1_1") (pintype "passive"))
      (node (ref "Q10") (pin "21") (pinfunction "AREF_21") (pintype "bidirectional"))
    )
    (net (code "27") (name "Net-(Q10-XTAL1)") (class "Default")
      (node (ref "C7") (pin "1") (pinfunction "1_1") (pintype "passive"))
      (node (ref "Q10") (pin "9") (pinfunction "XTAL1_9") (pintype "bidirectional"))
      (node (ref "X1") (pin "1") (pinfunction "1_1") (pintype "passive"))
    )
    (net (code "28") (name "Net-(Q10-XTAL2)") (class "Default")
      (node (ref "C8") (pin "1") (pinfunction "1_1") (pintype "passive"))
      (node (ref "Q10") (pin "10") (pinfunction "XTAL2_10") (pintype "bidirectional"))
      (node (ref "X1") (pin "3") (pinfunction "2_3") (pintype "passive"))
    )
    (net (code "29") (name "OC1A") (class "Default")
      (node (ref "Q10") (pin "16") (pinfunction "PB2_16") (pintype "bidirectional"))
      (node (ref "Q8") (pin "5") (pinfunction "PWM_5") (pintype "bidirectional"))
    )
    (net (code "30") (name "OC1B") (class "Default")
      (node (ref "Q10") (pin "15") (pinfunction "PB1_15") (pintype "bidirectional"))
      (node (ref "Q9") (pin "5") (pinfunction "PWM_5") (pintype "bidirectional"))
    )
    (net (code "31") (name "OC2B") (class "Default")
      (node (ref "Q10") (pin "5") (pinfunction "PD3_5") (pintype "bidirectional"))
      (node (ref "Q7") (pin "5") (pinfunction "PWM_5") (pintype "bidirectional"))
    )
    (net (code "32") (name "Q1") (class "Default")
      (node (ref "Q1") (pin "G") (pinfunction "G_G") (pintype "bidirectional"))
      (node (ref "Q7") (pin "3") (pinfunction "HO_3") (pintype "bidirectional"))
    )
    (net (code "33") (name "Q2") (class "Default")
      (node (ref "Q2") (pin "G") (pinfunction "G_G") (pintype "bidirectional"))
      (node (ref "R2") (pin "2") (pinfunction "2_2") (pintype "passive"))
    )
    (net (code "34") (name "Q3") (class "Default")
      (node (ref "Q3") (pin "G") (pinfunction "G_G") (pintype "bidirectional"))
      (node (ref "Q8") (pin "3") (pinfunction "HO_3") (pintype "bidirectional"))
    )
    (net (code "35") (name "Q4") (class "Default")
      (node (ref "Q4") (pin "G") (pinfunction "G_G") (pintype "bidirectional"))
      (node (ref "R4") (pin "2") (pinfunction "2_2") (pintype "passive"))
    )
    (net (code "36") (name "Q5") (class "Default")
      (node (ref "Q5") (pin "G") (pinfunction "G_G") (pintype "bidirectional"))
      (node (ref "Q9") (pin "3") (pinfunction "HO_3") (pintype "bidirectional"))
    )
    (net (code "37") (name "Q6") (class "Default")
      (node (ref "Q6") (pin "G") (pinfunction "G_G") (pintype "bidirectional"))
      (node (ref "R6") (pin "2") (pinfunction "2_2") (pintype "passive"))
    )
    (net (code "38") (name "RX") (class "Default")
      (node (ref "Q10") (pin "2") (pinfunction "PD0_2") (pintype "bidirectional"))
      (node (ref "Q11") (pin "2") (pinfunction "R_2") (pintype "bidirectional"))
    )
    (net (code "39") (name "SCK") (class "Default")
      (node (ref "J1") (pin "3") (pinfunction "3_3") (pintype "passive"))
      (node (ref "Q10") (pin "19") (pinfunction "PB5_19") (pintype "bidirectional"))
      (node (ref "R11") (pin "1") (pinfunction "1_1") (pintype "passive"))
      (node (ref "Z4") (pin "2") (pinfunction "P$2_2") (pintype "bidirectional"))
    )
    (net (code "40") (name "TEMP") (class "Default")
      (node (ref "Q10") (pin "26") (pinfunction "PC3_26") (pintype "bidirectional"))
      (node (ref "R14") (pin "2") (pinfunction "2_2") (pintype "passive"))
      (node (ref "R15") (pin "1") (pinfunction "1_1") (pintype "passive"))
    )
    (net (code "41") (name "TX") (class "Default")
      (node (ref "Q10") (pin "3") (pinfunction "PD1_3") (pintype "bidirectional"))
      (node (ref "Q11") (pin "3") (pinfunction "D_3") (pintype "bidirectional"))
    )
    (net (code "42") (name "VOLTAGE") (class "Default")
      (node (ref "C12") (pin "1") (pinfunction "1_1") (pintype "passive"))
      (node (ref "Q10") (pin "25") (pinfunction "PC2_25") (pintype "bidirectional"))
      (node (ref "R7") (pin "2") (pinfunction "2_2") (pintype "passive"))
      (node (ref "R8") (pin "1") (pinfunction "1_1") (pintype "passive"))
    )
    (net (code "43") (name "Y") (class "Default")
      (node (ref "J5") (pin "6") (pinfunction "6_6") (pintype "passive"))
      (node (ref "Q11") (pin "5") (pinfunction "Y_5") (pintype "bidirectional"))
    )
    (net (code "44") (name "Z") (class "Default")
      (node (ref "J5") (pin "5") (pinfunction "5_5") (pintype "passive"))
      (node (ref "Q11") (pin "6") (pinfunction "Z_6") (pintype "bidirectional"))
    )
    (net (code "45") (name "unconnected-(H1-Pad1)") (class "Default")
      (node (ref "H1") (pin "1") (pinfunction "1_1") (pintype "passive"))
    )
    (net (code "46") (name "unconnected-(H2-Pad1)") (class "Default")
      (node (ref "H2") (pin "1") (pinfunction "1_1") (pintype "passive"))
    )
    (net (code "47") (name "unconnected-(H3-Pad1)") (class "Default")
      (node (ref "H3") (pin "1") (pinfunction "1_1") (pintype "passive"))
    )
    (net (code "48") (name "unconnected-(H4-Pad1)") (class "Default")
      (node (ref "H4") (pin "1") (pinfunction "1_1") (pintype "passive"))
    )
    (net (code "49") (name "unconnected-(H5-Pad1)") (class "Default")
      (node (ref "H5") (pin "1") (pinfunction "1_1") (pintype "passive"))
    )
    (net (code "50") (name "unconnected-(H6-Pad1)") (class "Default")
      (node (ref "H6") (pin "1") (pinfunction "1_1") (pintype "passive"))
    )
    (net (code "51") (name "unconnected-(Q10-GND1-Pad22)") (class "Default")
      (node (ref "Q10") (pin "22") (pinfunction "GND1_22") (pintype "bidirectional"))
    )
    (net (code "52") (name "unconnected-(Q10-PC0-Pad23)") (class "Default")
      (node (ref "Q10") (pin "23") (pinfunction "PC0_23") (pintype "bidirectional"))
    )
    (net (code "53") (name "unconnected-(Q10-PC1-Pad24)") (class "Default")
      (node (ref "Q10") (pin "24") (pinfunction "PC1_24") (pintype "bidirectional"))
    )
    (net (code "54") (name "unconnected-(Q10-PC4-Pad27)") (class "Default")
      (node (ref "Q10") (pin "27") (pinfunction "PC4_27") (pintype "bidirectional"))
    )
    (net (code "55") (name "unconnected-(Q10-PD2-Pad4)") (class "Default")
      (node (ref "Q10") (pin "4") (pinfunction "PD2_4") (pintype "bidirectional"))
    )
    (net (code "56") (name "unconnected-(Q10-PD4-Pad6)") (class "Default")
      (node (ref "Q10") (pin "6") (pinfunction "PD4_6") (pintype "bidirectional"))
    )
    (net (code "57") (name "unconnected-(Q10-PD5-Pad11)") (class "Default")
      (node (ref "Q10") (pin "11") (pinfunction "PD5_11") (pintype "bidirectional"))
    )
    (net (code "58") (name "unconnected-(Q10-PD6-Pad12)") (class "Default")
      (node (ref "Q10") (pin "12") (pinfunction "PD6_12") (pintype "bidirectional"))
    )
    (net (code "59") (name "unconnected-(Q15-{slash}FAULT-Pad7)") (class "Default")
      (node (ref "Q15") (pin "7") (pinfunction "/FAULT_7") (pintype "bidirectional"))
    )
  )
)
